# schematic.net
KiCad netlist of a schematic drawn in EasyEDA
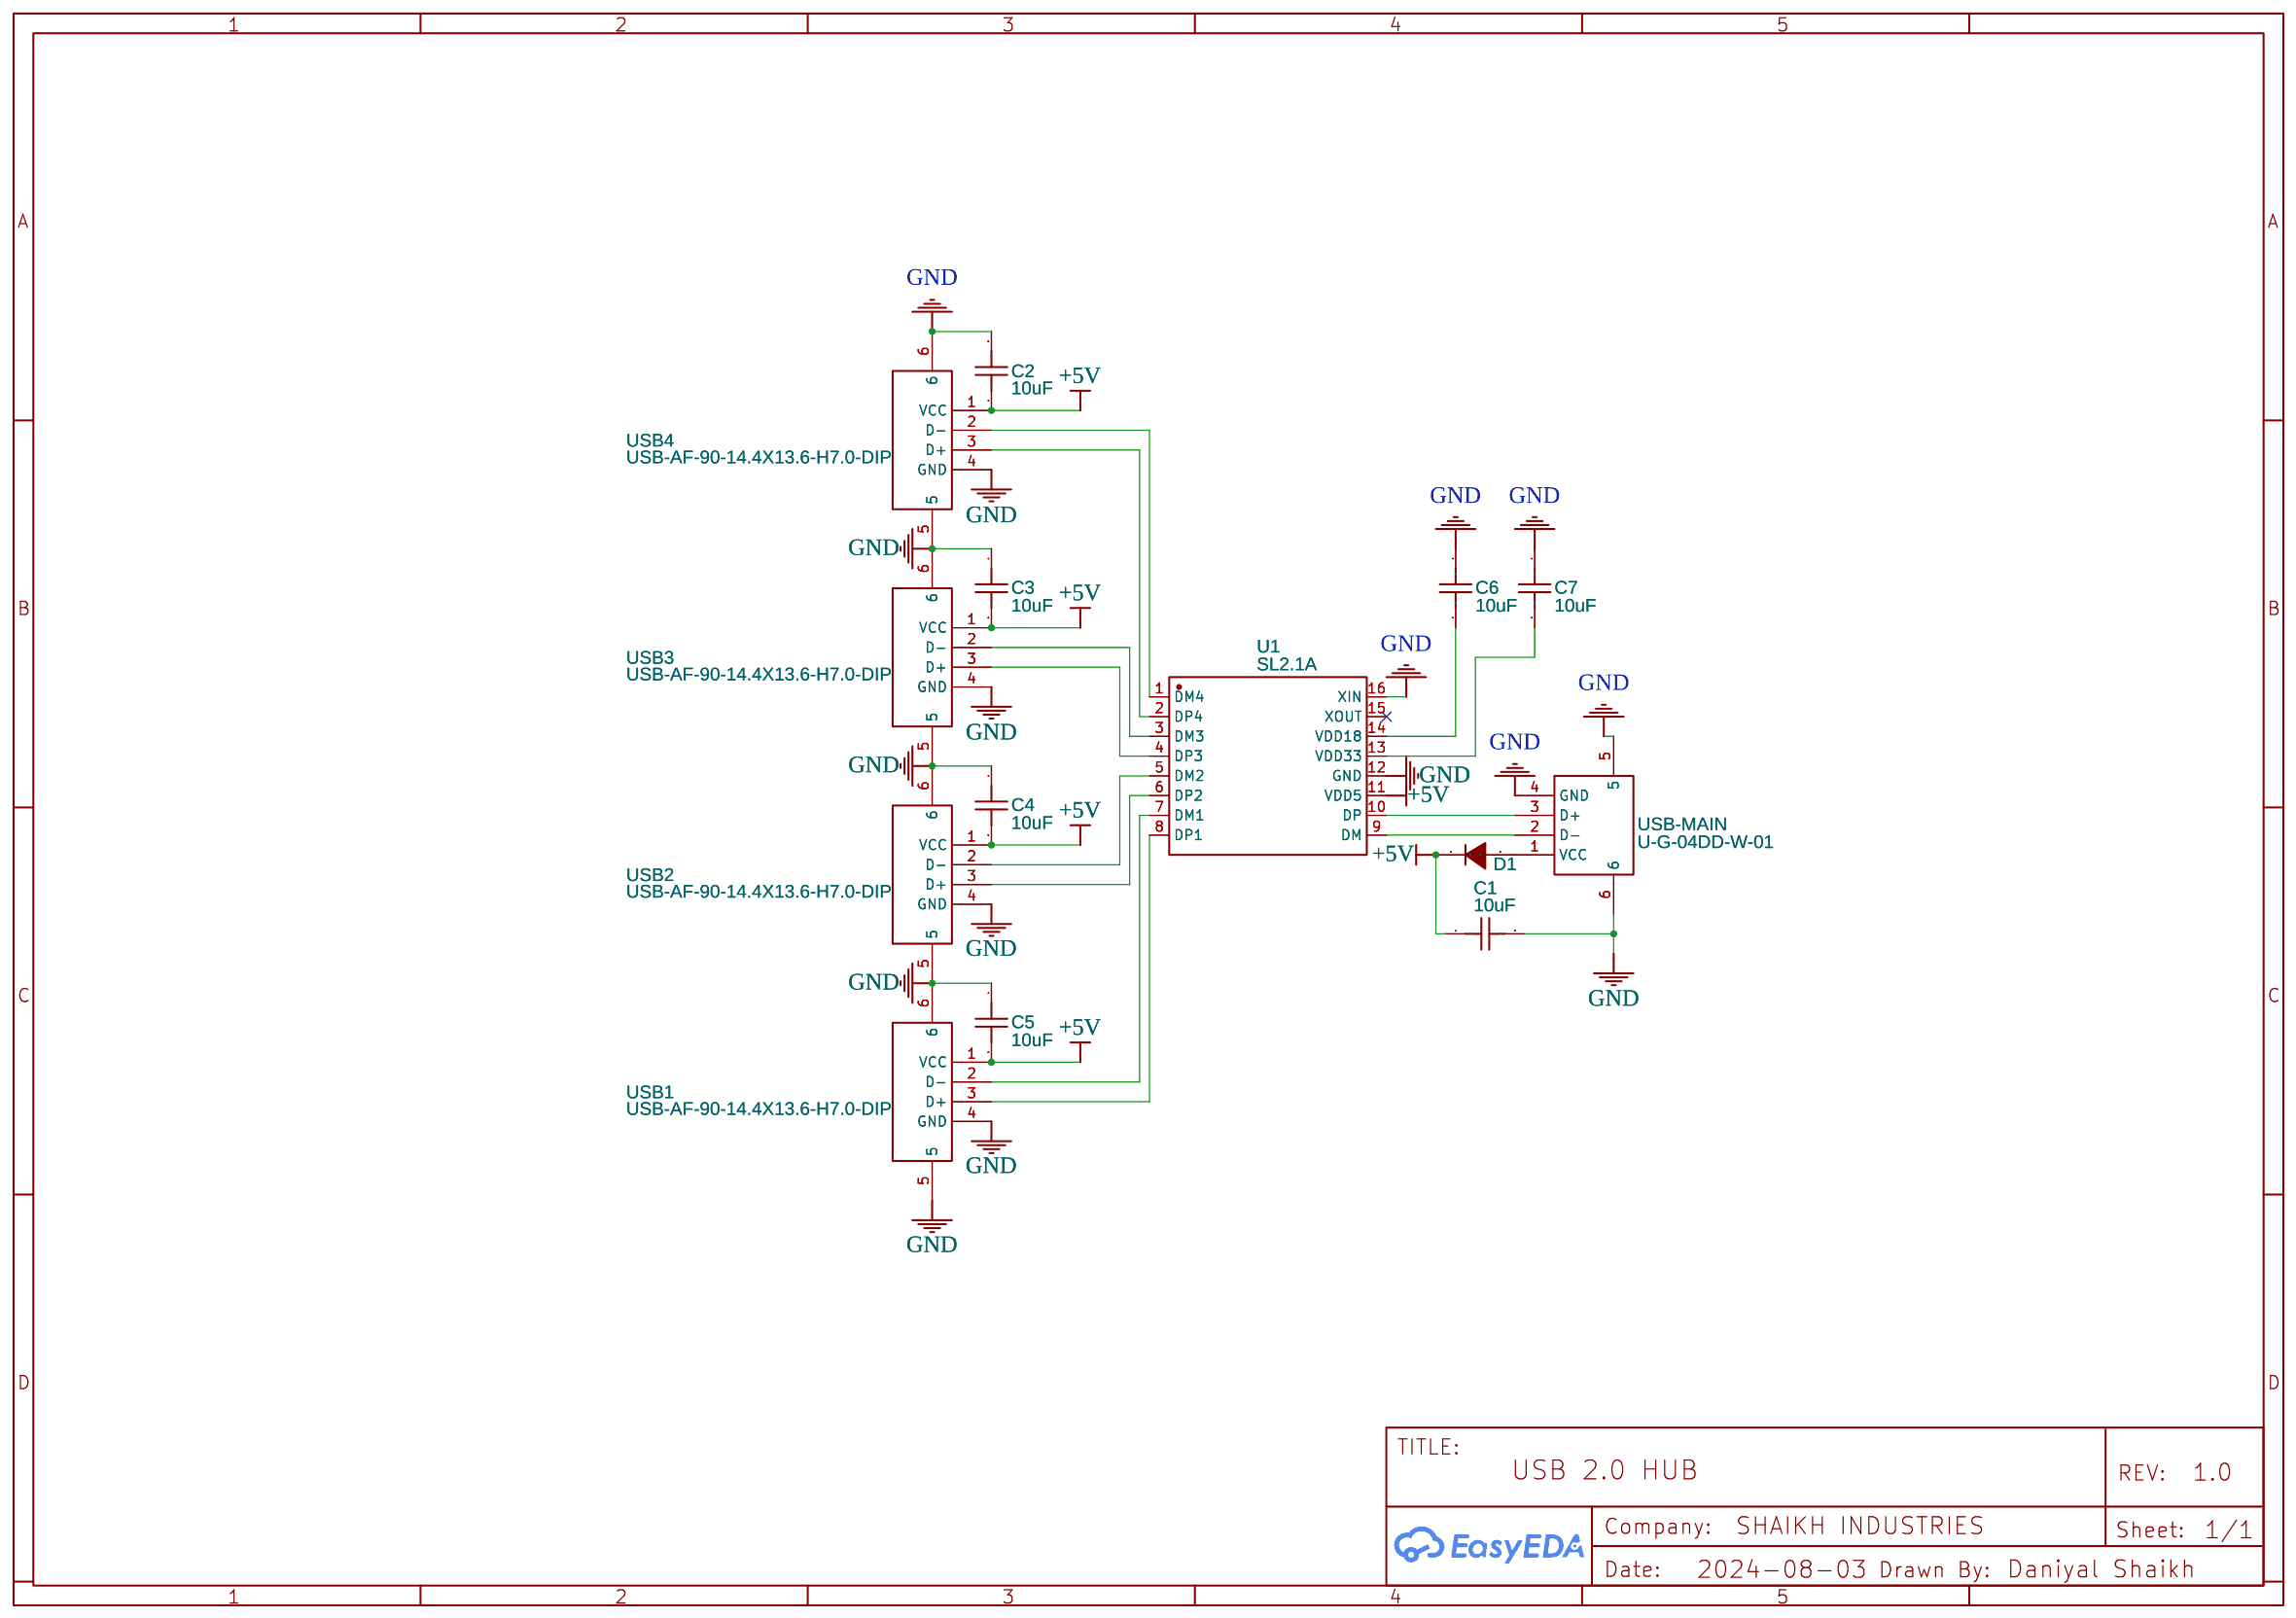
[diagram p0: schematic sheet]

(export (version "E")
  (design (tool "Eeschema 10.0.6"))
  (components
    (comp (ref "C1")
      (value "10uF")
      (fields
        (field (name "Manufacturer Part") "CL10A106KP8NNNC")
        (field (name "Manufacturer") "SAMSUNG(三星)")
      )
      (libsource (lib "") (part "CL10A106KP8NNNC_1"))
    )
    (comp (ref "C2")
      (value "10uF")
      (fields
        (field (name "Manufacturer Part") "CL10A106KP8NNNC")
        (field (name "Manufacturer") "SAMSUNG(三星)")
      )
      (libsource (lib "") (part "CL10A106KP8NNNC_2"))
    )
    (comp (ref "C3")
      (value "10uF")
      (fields
        (field (name "Manufacturer Part") "CL10A106KP8NNNC")
        (field (name "Manufacturer") "SAMSUNG(三星)")
      )
      (libsource (lib "") (part "CL10A106KP8NNNC"))
    )
    (comp (ref "C4")
      (value "10uF")
      (fields
        (field (name "Manufacturer Part") "CL10A106KP8NNNC")
        (field (name "Manufacturer") "SAMSUNG(三星)")
      )
      (libsource (lib "") (part "CL10A106KP8NNNC"))
    )
    (comp (ref "C5")
      (value "10uF")
      (fields
        (field (name "Manufacturer Part") "CL10A106KP8NNNC")
        (field (name "Manufacturer") "SAMSUNG(三星)")
      )
      (libsource (lib "") (part "CL10A106KP8NNNC"))
    )
    (comp (ref "C6")
      (value "10uF")
      (fields
        (field (name "Manufacturer Part") "CL10A106KP8NNNC")
        (field (name "Manufacturer") "SAMSUNG(三星)")
      )
      (libsource (lib "") (part "CL10A106KP8NNNC"))
    )
    (comp (ref "C7")
      (value "10uF")
      (fields
        (field (name "Manufacturer Part") "CL10A106KP8NNNC")
        (field (name "Manufacturer") "SAMSUNG(三星)")
      )
      (libsource (lib "") (part "CL10A106KP8NNNC"))
    )
    (comp (ref "D1")
      (value "NSR0320MW2T1G")
      (fields (field (name "Manufacturer") "onsemi(安森美)"))
      (libsource (lib "") (part "NSR0320MW2T1G"))
    )
    (comp (ref "U1")
      (value "SL2.1A")
      (fields (field (name "Manufacturer") "CoreChips(和芯润德)"))
      (libsource (lib "") (part "SL2.1A"))
    )
    (comp (ref "USB-MAIN")
      (value "U-G-04DD-W-01")
      (fields (field (name "Manufacturer Part") "U-G-O4DD-W-1") (field (name "Manufacturer") "韩国韩荣"))
      (libsource (lib "") (part "U-G-04DD-W-01"))
    )
    (comp (ref "USB1")
      (value "USB-AF-90-14.4X13.6-H7.0-DIP")
      (fields (field (name "Manufacturer Part") "903-131A1011D10100") (field (name "Manufacturer") "精拓金"))
      (libsource (lib "") (part "USB-AF-90-14.4X13.6-H7.0-DIP"))
    )
    (comp (ref "USB2")
      (value "USB-AF-90-14.4X13.6-H7.0-DIP")
      (fields (field (name "Manufacturer Part") "903-131A1011D10100") (field (name "Manufacturer") "精拓金"))
      (libsource (lib "") (part "USB-AF-90-14.4X13.6-H7.0-DIP"))
    )
    (comp (ref "USB3")
      (value "USB-AF-90-14.4X13.6-H7.0-DIP")
      (fields (field (name "Manufacturer Part") "903-131A1011D10100") (field (name "Manufacturer") "精拓金"))
      (libsource (lib "") (part "USB-AF-90-14.4X13.6-H7.0-DIP"))
    )
    (comp (ref "USB4")
      (value "USB-AF-90-14.4X13.6-H7.0-DIP")
      (fields (field (name "Manufacturer Part") "903-131A1011D10100") (field (name "Manufacturer") "精拓金"))
      (libsource (lib "") (part "USB-AF-90-14.4X13.6-H7.0-DIP"))
    )
  )
  (nets
    (net (code "1") (name "+5V") (class "Default")
      (node (ref "C1") (pin "1") (pinfunction "1_1") (pintype "unspecified"))
      (node (ref "C2") (pin "1") (pinfunction "1_1") (pintype "unspecified"))
      (node (ref "C3") (pin "2") (pinfunction "2_2") (pintype "unspecified"))
      (node (ref "C4") (pin "2") (pinfunction "2_2") (pintype "unspecified"))
      (node (ref "C5") (pin "2") (pinfunction "2_2") (pintype "unspecified"))
      (node (ref "D1") (pin "1") (pinfunction "C_1") (pintype "unspecified"))
      (node (ref "U1") (pin "11") (pinfunction "VDD5_11") (pintype "unspecified"))
      (node (ref "USB1") (pin "1") (pinfunction "VCC_1") (pintype "unspecified"))
      (node (ref "USB2") (pin "1") (pinfunction "VCC_1") (pintype "unspecified"))
      (node (ref "USB3") (pin "1") (pinfunction "VCC_1") (pintype "unspecified"))
      (node (ref "USB4") (pin "1") (pinfunction "VCC_1") (pintype "unspecified"))
    )
    (net (code "2") (name "GND") (class "Default")
      (node (ref "C1") (pin "2") (pinfunction "2_2") (pintype "unspecified"))
      (node (ref "C2") (pin "2") (pinfunction "2_2") (pintype "unspecified"))
      (node (ref "C3") (pin "1") (pinfunction "1_1") (pintype "unspecified"))
      (node (ref "C4") (pin "1") (pinfunction "1_1") (pintype "unspecified"))
      (node (ref "C5") (pin "1") (pinfunction "1_1") (pintype "unspecified"))
      (node (ref "C6") (pin "1") (pinfunction "1_1") (pintype "unspecified"))
      (node (ref "C7") (pin "1") (pinfunction "1_1") (pintype "unspecified"))
      (node (ref "U1") (pin "12") (pinfunction "GND_12") (pintype "unspecified"))
      (node (ref "U1") (pin "16") (pinfunction "XIN_16") (pintype "unspecified"))
      (node (ref "USB-MAIN") (pin "4") (pinfunction "GND_4") (pintype "unspecified"))
      (node (ref "USB-MAIN") (pin "5") (pinfunction "5_5") (pintype "unspecified"))
      (node (ref "USB-MAIN") (pin "6") (pinfunction "6_6") (pintype "unspecified"))
      (node (ref "USB1") (pin "4") (pinfunction "GND_4") (pintype "unspecified"))
      (node (ref "USB1") (pin "5") (pinfunction "5_5") (pintype "unspecified"))
      (node (ref "USB1") (pin "6") (pinfunction "6_6") (pintype "unspecified"))
      (node (ref "USB2") (pin "4") (pinfunction "GND_4") (pintype "unspecified"))
      (node (ref "USB2") (pin "5") (pinfunction "5_5") (pintype "unspecified"))
      (node (ref "USB2") (pin "6") (pinfunction "6_6") (pintype "unspecified"))
      (node (ref "USB3") (pin "4") (pinfunction "GND_4") (pintype "unspecified"))
      (node (ref "USB3") (pin "5") (pinfunction "5_5") (pintype "unspecified"))
      (node (ref "USB3") (pin "6") (pinfunction "6_6") (pintype "unspecified"))
      (node (ref "USB4") (pin "4") (pinfunction "GND_4") (pintype "unspecified"))
      (node (ref "USB4") (pin "5") (pinfunction "5_5") (pintype "unspecified"))
      (node (ref "USB4") (pin "6") (pinfunction "6_6") (pintype "unspecified"))
    )
    (net (code "3") (name "Net-(D1-A)") (class "Default")
      (node (ref "D1") (pin "2") (pinfunction "A_2") (pintype "unspecified"))
      (node (ref "USB-MAIN") (pin "1") (pinfunction "VCC_1") (pintype "unspecified"))
    )
    (net (code "4") (name "Net-(U1-DM)") (class "Default")
      (node (ref "U1") (pin "9") (pinfunction "DM_9") (pintype "unspecified"))
      (node (ref "USB-MAIN") (pin "2") (pinfunction "D-_2") (pintype "unspecified"))
    )
    (net (code "5") (name "Net-(U1-DM1)") (class "Default")
      (node (ref "U1") (pin "7") (pinfunction "DM1_7") (pintype "unspecified"))
      (node (ref "USB1") (pin "2") (pinfunction "D-_2") (pintype "unspecified"))
    )
    (net (code "6") (name "Net-(U1-DM2)") (class "Default")
      (node (ref "U1") (pin "5") (pinfunction "DM2_5") (pintype "unspecified"))
      (node (ref "USB2") (pin "2") (pinfunction "D-_2") (pintype "unspecified"))
    )
    (net (code "7") (name "Net-(U1-DM3)") (class "Default")
      (node (ref "U1") (pin "3") (pinfunction "DM3_3") (pintype "unspecified"))
      (node (ref "USB3") (pin "2") (pinfunction "D-_2") (pintype "unspecified"))
    )
    (net (code "8") (name "Net-(U1-DM4)") (class "Default")
      (node (ref "U1") (pin "1") (pinfunction "DM4_1") (pintype "unspecified"))
      (node (ref "USB4") (pin "2") (pinfunction "D-_2") (pintype "unspecified"))
    )
    (net (code "9") (name "Net-(U1-DP)") (class "Default")
      (node (ref "U1") (pin "10") (pinfunction "DP_10") (pintype "unspecified"))
      (node (ref "USB-MAIN") (pin "3") (pinfunction "D+_3") (pintype "unspecified"))
    )
    (net (code "10") (name "Net-(U1-DP1)") (class "Default")
      (node (ref "U1") (pin "8") (pinfunction "DP1_8") (pintype "unspecified"))
      (node (ref "USB1") (pin "3") (pinfunction "D+_3") (pintype "unspecified"))
    )
    (net (code "11") (name "Net-(U1-DP2)") (class "Default")
      (node (ref "U1") (pin "6") (pinfunction "DP2_6") (pintype "unspecified"))
      (node (ref "USB2") (pin "3") (pinfunction "D+_3") (pintype "unspecified"))
    )
    (net (code "12") (name "Net-(U1-DP3)") (class "Default")
      (node (ref "U1") (pin "4") (pinfunction "DP3_4") (pintype "unspecified"))
      (node (ref "USB3") (pin "3") (pinfunction "D+_3") (pintype "unspecified"))
    )
    (net (code "13") (name "Net-(U1-DP4)") (class "Default")
      (node (ref "U1") (pin "2") (pinfunction "DP4_2") (pintype "unspecified"))
      (node (ref "USB4") (pin "3") (pinfunction "D+_3") (pintype "unspecified"))
    )
    (net (code "14") (name "Net-(U1-VDD18)") (class "Default")
      (node (ref "C6") (pin "2") (pinfunction "2_2") (pintype "unspecified"))
      (node (ref "U1") (pin "14") (pinfunction "VDD18_14") (pintype "unspecified"))
    )
    (net (code "15") (name "Net-(U1-VDD33)") (class "Default")
      (node (ref "C7") (pin "2") (pinfunction "2_2") (pintype "unspecified"))
      (node (ref "U1") (pin "13") (pinfunction "VDD33_13") (pintype "unspecified"))
    )
    (net (code "16") (name "unconnected-(U1-XOUT-Pad15)") (class "Default")
      (node (ref "U1") (pin "15") (pinfunction "XOUT_15") (pintype "unspecified+no_connect"))
    )
  )
)
